# WebCamLight_Leds_RevB.net
KiCad netlist of a schematic drawn in Altium Designer
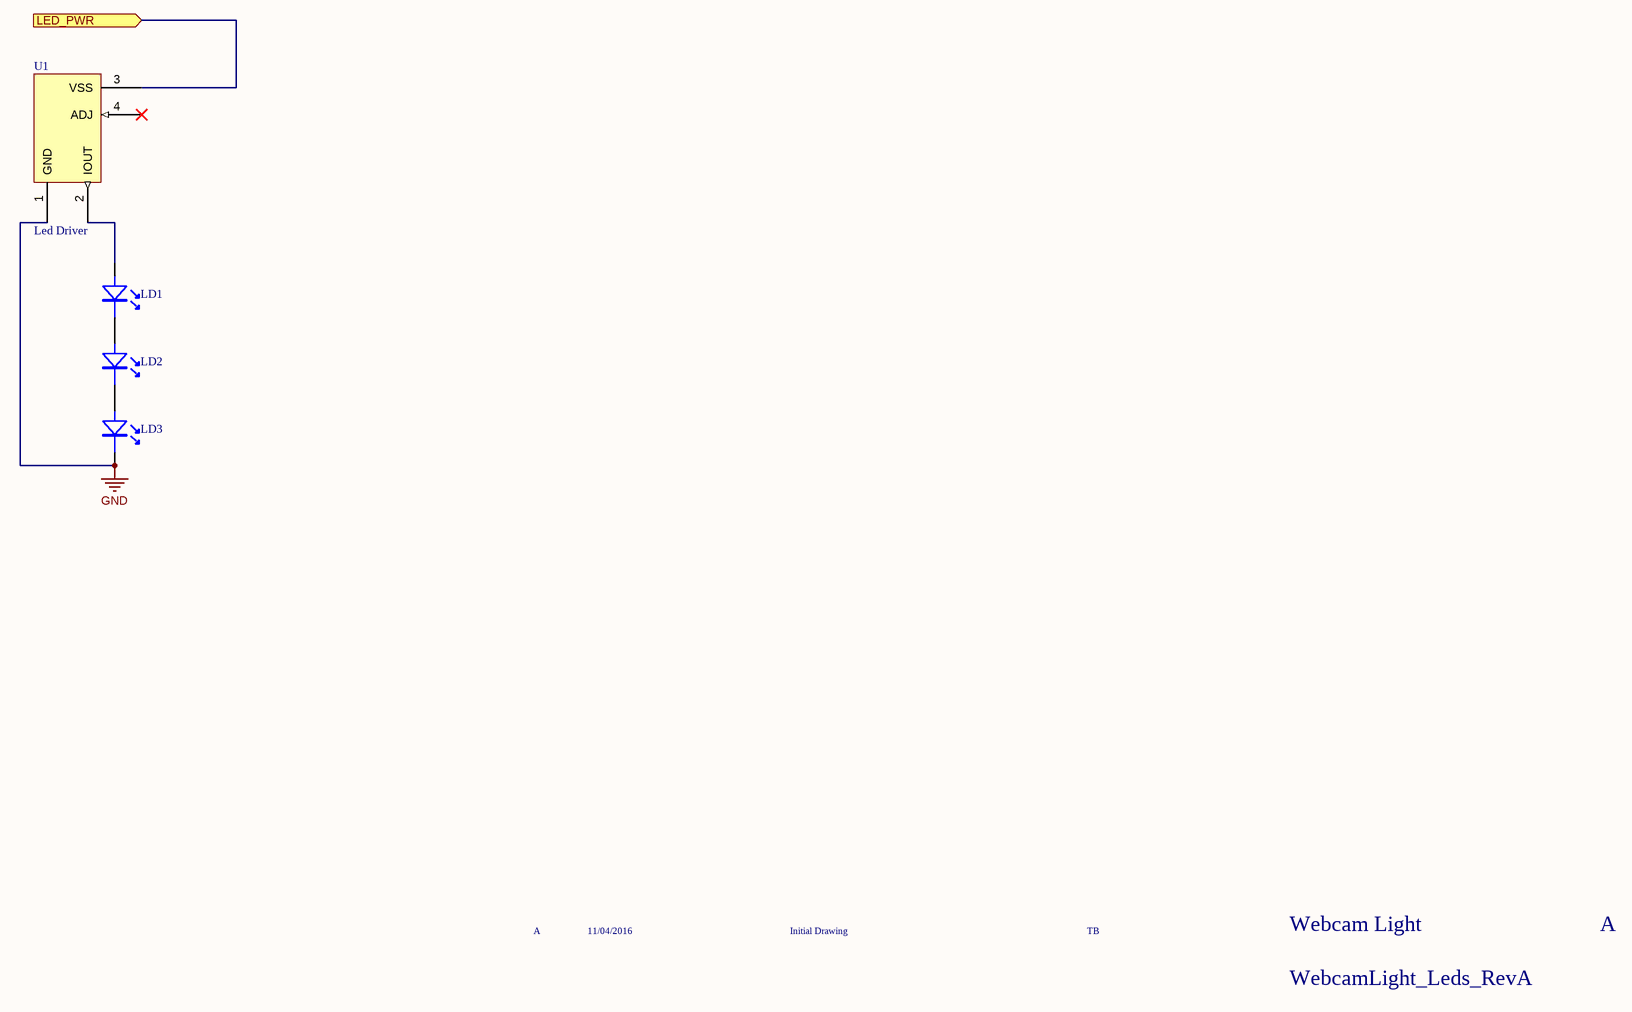
[diagram p0: WebCamLight_Leds_RevB.SchDoc]

(export (version "E")
  (design (tool "Eeschema 10.0.6"))
  (components
    (comp (ref "LD1")
      (value "Green LED 0805")
      (footprint "Wurth_1206_Led")
      (description "WL-SMCW SMD CHIP LED WATERCLEAR")
      (fields (field (name "MANUFACTURER") "Wurth"))
      (libsource (lib "Semiconductors") (part "LED_White_1206"))
    )
    (comp (ref "LD2")
      (value "Green LED 0805")
      (footprint "Wurth_1206_Led")
      (description "WL-SMCW SMD CHIP LED WATERCLEAR")
      (fields (field (name "MANUFACTURER") "Wurth"))
      (libsource (lib "Semiconductors") (part "LED_White_1206"))
    )
    (comp (ref "LD3")
      (value "Green LED 0805")
      (footprint "Wurth_1206_Led")
      (description "WL-SMCW SMD CHIP LED WATERCLEAR")
      (fields (field (name "MANUFACTURER") "Wurth"))
      (libsource (lib "Semiconductors") (part "LED_White_1206"))
    )
    (comp (ref "U1")
      (value "Led Driver")
      (footprint "SOT192P237X110-4M")
      (description "20-60mA Led Driver")
      (fields (field (name "MANUFACTURER") "Infineon"))
      (libsource (lib "IC") (part "IC_LED_DRV_BCR401R"))
    )
  )
  (nets
    (net (code "1") (name "/LED_PWR") (class "Default")
      (node (ref "U1") (pin "3") (pinfunction "VSS_3") (pintype "power_in"))
    )
    (net (code "2") (name "GND") (class "Default")
      (node (ref "LD3") (pin "1") (pintype "passive"))
      (node (ref "U1") (pin "1") (pinfunction "GND_1") (pintype "power_in"))
    )
    (net (code "3") (name "Net-(LD1-Pad1)") (class "Default")
      (node (ref "LD1") (pin "1") (pintype "passive"))
      (node (ref "LD2") (pin "2") (pintype "passive"))
    )
    (net (code "4") (name "Net-(LD2-Pad1)") (class "Default")
      (node (ref "LD2") (pin "1") (pintype "passive"))
      (node (ref "LD3") (pin "2") (pintype "passive"))
    )
    (net (code "5") (name "Net-(U1-IOUT)") (class "Default")
      (node (ref "LD1") (pin "2") (pintype "passive"))
      (node (ref "U1") (pin "2") (pinfunction "IOUT_2") (pintype "output"))
    )
    (net (code "6") (name "unconnected-(U1-ADJ-Pad4)") (class "Default")
      (node (ref "U1") (pin "4") (pinfunction "ADJ_4") (pintype "input+no_connect"))
    )
  )
)
